# gpi-filter3.net
KiCad netlist of a schematic drawn in EAGLE
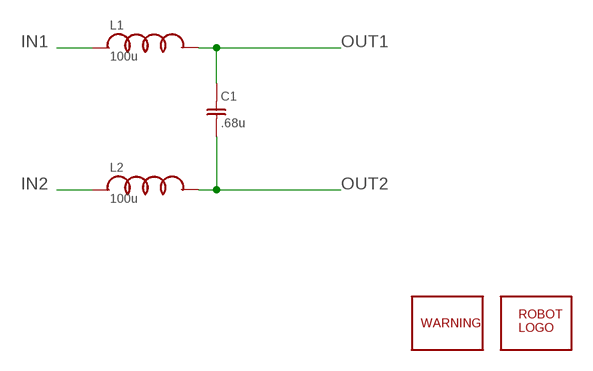
[diagram p0: schematic, sheet 1]

(export (version "E")
  (design (tool "Eeschema 10.0.6"))
  (components
    (comp (ref "C1")
      (value ".68u")
      (footprint "eagle-import:R46KI36804P1M")
      (libsource (lib "eagle-import") (part "CR46KI36804P1M"))
    )
    (comp (ref "L1")
      (value "100u")
      (footprint "eagle-import:AIRD03")
      (libsource (lib "eagle-import") (part "LAIRD03"))
    )
    (comp (ref "L2")
      (value "100u")
      (footprint "eagle-import:AIRD03")
      (libsource (lib "eagle-import") (part "LAIRD03"))
    )
    (comp (ref "U$1")
      (value "ROBOTMAN-LOGO")
      (footprint "eagle-import:ROBOTMAN-LOGO")
      (libsource (lib "eagle-import") (part "ROBOTMAN-LOGO"))
    )
    (comp (ref "U$2")
      (value "SYMBOL-WARNING")
      (footprint "eagle-import:SYMBOL-WARNING")
      (libsource (lib "eagle-import") (part "SYMBOL-WARNING"))
    )
  )
  (nets
    (net (code "1") (name "/IN1") (class "Default")
      (node (ref "L1") (pin "P$1") (pinfunction "P$1_P$1") (pintype "passive"))
    )
    (net (code "2") (name "/IN2") (class "Default")
      (node (ref "L2") (pin "P$1") (pinfunction "P$1_P$1") (pintype "passive"))
    )
    (net (code "3") (name "/OUT1") (class "Default")
      (node (ref "C1") (pin "P$1") (pinfunction "P$1_P$1") (pintype "passive"))
      (node (ref "L1") (pin "P$2") (pinfunction "P$2_P$2") (pintype "passive"))
    )
    (net (code "4") (name "/OUT2") (class "Default")
      (node (ref "C1") (pin "P$2") (pinfunction "P$2_P$2") (pintype "passive"))
      (node (ref "L2") (pin "P$2") (pinfunction "P$2_P$2") (pintype "passive"))
    )
  )
)
